# Mosaic-G5.net
KiCad netlist of a schematic drawn in Altium Designer
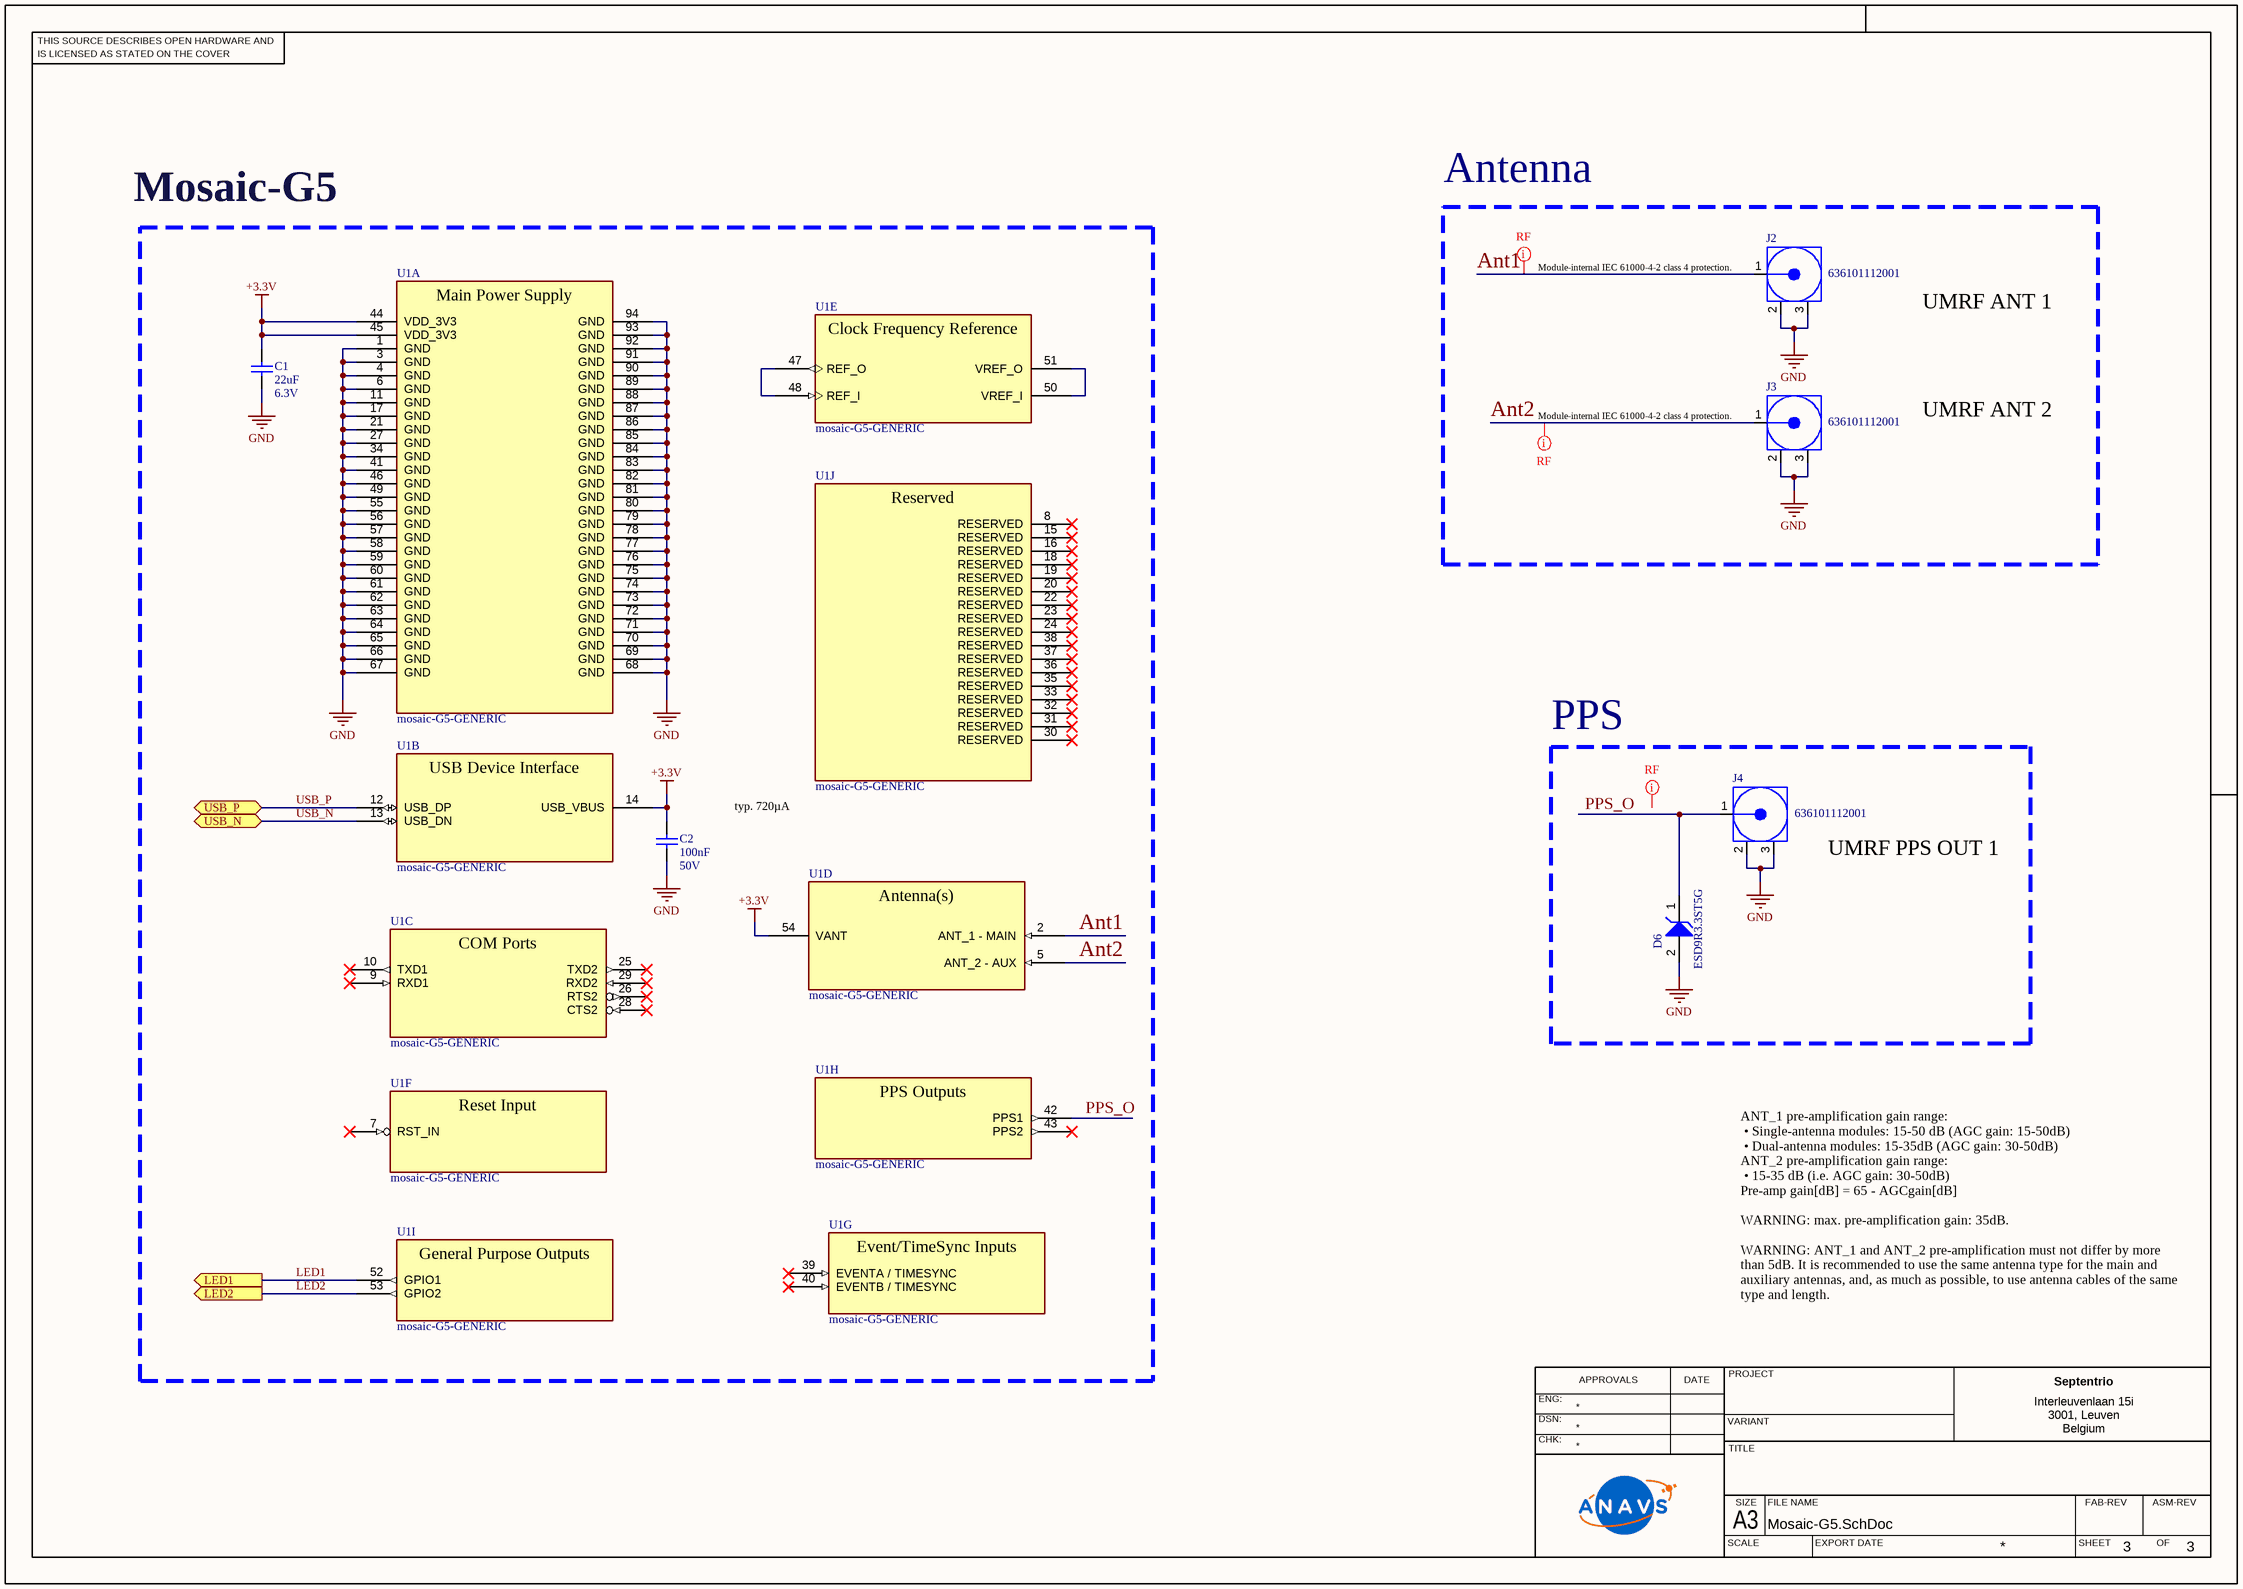
[diagram p0: Mosaic-G5.SchDoc]

(export (version "E")
  (design (tool "Eeschema 10.0.6"))
  (components
    (comp (ref "C1")
      (value "22uF")
      (footprint "CAPC1608X100X20ML10")
      (description "MLCC, 22 uF, 0603, 6.3 V, 20%, X5R")
      (fields
        (field (name "VOLTAGE") "6.3V")
        (field (name "TOLERANCE") "20%")
        (field (name "Comment") "C1608X5R0J226M080AC")
      )
      (libsource (lib "ANavS GmbH") (part "CAP"))
    )
    (comp (ref "C2")
      (value "GCM155R71H104KE02D")
      (footprint "CAP0402C")
      (description "MLCC, 100 nF, 0402, 50 V, 10%, X7R")
      (fields
        (field (name "CAPACITANCE") "100nF")
        (field (name "TOLERANCE") "10%")
        (field (name "VOLTAGE") "50V")
      )
      (libsource (lib "ANavS GmbH") (part "CAP"))
    )
    (comp (ref "D6")
      (value "ESD9R3.3ST5G")
      (footprint "ONSC-SOD-923-2-514AB-01_V")
      (description "ESD9R3.3S Series 4.8 V 0.5 pF Uni-Directional ESD Protection Diode - SOD-923")
      (libsource (lib "ANavS GmbH") (part "ONSC-K1A2-2_A"))
    )
    (comp (ref "J2")
      (value "636101112001")
      (footprint "63610111x001")
      (description "Rf Conn, Umrf, Jack, 50 Ohm, Pcb Rohs Compliant: Yes")
      (libsource (lib "ANavS GmbH") (part "Plug_2GND"))
    )
    (comp (ref "J3")
      (value "636101112001")
      (footprint "63610111x001")
      (description "Rf Conn, Umrf, Jack, 50 Ohm, Pcb Rohs Compliant: Yes")
      (libsource (lib "ANavS GmbH") (part "Plug_2GND"))
    )
    (comp (ref "J4")
      (value "636101112001")
      (footprint "63610111x001")
      (description "Rf Conn, Umrf, Jack, 50 Ohm, Pcb Rohs Compliant: Yes")
      (libsource (lib "ANavS GmbH") (part "Plug_2GND"))
    )
    (comp (ref "U1")
      (value "mosaic-G5-GENERIC")
      (footprint "mosaic-G5-GENERIC-Footprint")
      (description "mosaic-G5 GNSS Module - Low-power multi-band multi-constellation GNSS receiver.")
      (fields (field (name "MANUFACTURER") "septentrio"))
      (libsource (lib "ANavS GmbH") (part "mosaic-G5-Symbol"))
    )
  )
  (nets
    (net (code "1") (name "+3.3V") (class "Default")
      (node (ref "C1") (pin "2") (pinfunction "2_2") (pintype "passive"))
      (node (ref "C2") (pin "2") (pinfunction "2_2") (pintype "passive"))
      (node (ref "U1") (pin "14") (pinfunction "USB_VBUS_14") (pintype "power_in"))
      (node (ref "U1") (pin "44") (pinfunction "VDD_3V3_44") (pintype "power_in"))
      (node (ref "U1") (pin "45") (pinfunction "VDD_3V3_45") (pintype "power_in"))
      (node (ref "U1") (pin "54") (pinfunction "VANT_54") (pintype "power_in"))
    )
    (net (code "2") (name "/Ant1") (class "Default")
      (node (ref "J2") (pin "1") (pinfunction "Signal_1") (pintype "passive"))
      (node (ref "U1") (pin "2") (pinfunction "ANT_1_-_MAIN_2") (pintype "input"))
    )
    (net (code "3") (name "/Ant2") (class "Default")
      (node (ref "J3") (pin "1") (pinfunction "Signal_1") (pintype "passive"))
      (node (ref "U1") (pin "5") (pinfunction "ANT_2_-_AUX_5") (pintype "input"))
    )
    (net (code "4") (name "/LED1") (class "Default")
      (node (ref "U1") (pin "52") (pinfunction "GPIO1_52") (pintype "output"))
    )
    (net (code "5") (name "/LED2") (class "Default")
      (node (ref "U1") (pin "53") (pinfunction "GPIO2_53") (pintype "output"))
    )
    (net (code "6") (name "/PPS_O") (class "Default")
      (node (ref "D6") (pin "1") (pinfunction "K_1") (pintype "passive"))
      (node (ref "J4") (pin "1") (pinfunction "Signal_1") (pintype "passive"))
      (node (ref "U1") (pin "42") (pinfunction "PPS1_42") (pintype "output"))
    )
    (net (code "7") (name "/USB_N") (class "Default")
      (node (ref "U1") (pin "13") (pinfunction "USB_DN_13") (pintype "bidirectional"))
    )
    (net (code "8") (name "/USB_P") (class "Default")
      (node (ref "U1") (pin "12") (pinfunction "USB_DP_12") (pintype "bidirectional"))
    )
    (net (code "9") (name "GND") (class "Default")
      (node (ref "C1") (pin "1") (pinfunction "1_1") (pintype "passive"))
      (node (ref "C2") (pin "1") (pinfunction "1_1") (pintype "passive"))
      (node (ref "D6") (pin "2") (pinfunction "A_2") (pintype "passive"))
      (node (ref "J2") (pin "2") (pinfunction "GND_2") (pintype "passive"))
      (node (ref "J2") (pin "3") (pinfunction "GND_3") (pintype "passive"))
      (node (ref "J3") (pin "2") (pinfunction "GND_2") (pintype "passive"))
      (node (ref "J3") (pin "3") (pinfunction "GND_3") (pintype "passive"))
      (node (ref "J4") (pin "2") (pinfunction "GND_2") (pintype "passive"))
      (node (ref "J4") (pin "3") (pinfunction "GND_3") (pintype "passive"))
      (node (ref "U1") (pin "1") (pinfunction "GND_1") (pintype "power_in"))
      (node (ref "U1") (pin "11") (pinfunction "GND_11") (pintype "power_in"))
      (node (ref "U1") (pin "17") (pinfunction "GND_17") (pintype "power_in"))
      (node (ref "U1") (pin "21") (pinfunction "GND_21") (pintype "power_in"))
      (node (ref "U1") (pin "27") (pinfunction "GND_27") (pintype "power_in"))
      (node (ref "U1") (pin "3") (pinfunction "GND_3") (pintype "power_in"))
      (node (ref "U1") (pin "34") (pinfunction "GND_34") (pintype "power_in"))
      (node (ref "U1") (pin "4") (pinfunction "GND_4") (pintype "power_in"))
      (node (ref "U1") (pin "41") (pinfunction "GND_41") (pintype "power_in"))
      (node (ref "U1") (pin "46") (pinfunction "GND_46") (pintype "power_in"))
      (node (ref "U1") (pin "49") (pinfunction "GND_49") (pintype "power_in"))
      (node (ref "U1") (pin "55") (pinfunction "GND_55") (pintype "power_in"))
      (node (ref "U1") (pin "56") (pinfunction "GND_56") (pintype "power_in"))
      (node (ref "U1") (pin "57") (pinfunction "GND_57") (pintype "power_in"))
      (node (ref "U1") (pin "58") (pinfunction "GND_58") (pintype "power_in"))
      (node (ref "U1") (pin "59") (pinfunction "GND_59") (pintype "power_in"))
      (node (ref "U1") (pin "6") (pinfunction "GND_6") (pintype "power_in"))
      (node (ref "U1") (pin "60") (pinfunction "GND_60") (pintype "power_in"))
      (node (ref "U1") (pin "61") (pinfunction "GND_61") (pintype "power_in"))
      (node (ref "U1") (pin "62") (pinfunction "GND_62") (pintype "power_in"))
      (node (ref "U1") (pin "63") (pinfunction "GND_63") (pintype "power_in"))
      (node (ref "U1") (pin "64") (pinfunction "GND_64") (pintype "power_in"))
      (node (ref "U1") (pin "65") (pinfunction "GND_65") (pintype "power_in"))
      (node (ref "U1") (pin "66") (pinfunction "GND_66") (pintype "power_in"))
      (node (ref "U1") (pin "67") (pinfunction "GND_67") (pintype "power_in"))
      (node (ref "U1") (pin "68") (pinfunction "GND_68") (pintype "power_in"))
      (node (ref "U1") (pin "69") (pinfunction "GND_69") (pintype "power_in"))
      (node (ref "U1") (pin "70") (pinfunction "GND_70") (pintype "power_in"))
      (node (ref "U1") (pin "71") (pinfunction "GND_71") (pintype "power_in"))
      (node (ref "U1") (pin "72") (pinfunction "GND_72") (pintype "power_in"))
      (node (ref "U1") (pin "73") (pinfunction "GND_73") (pintype "power_in"))
      (node (ref "U1") (pin "74") (pinfunction "GND_74") (pintype "power_in"))
      (node (ref "U1") (pin "75") (pinfunction "GND_75") (pintype "power_in"))
      (node (ref "U1") (pin "76") (pinfunction "GND_76") (pintype "power_in"))
      (node (ref "U1") (pin "77") (pinfunction "GND_77") (pintype "power_in"))
      (node (ref "U1") (pin "78") (pinfunction "GND_78") (pintype "power_in"))
      (node (ref "U1") (pin "79") (pinfunction "GND_79") (pintype "power_in"))
      (node (ref "U1") (pin "80") (pinfunction "GND_80") (pintype "power_in"))
      (node (ref "U1") (pin "81") (pinfunction "GND_81") (pintype "power_in"))
      (node (ref "U1") (pin "82") (pinfunction "GND_82") (pintype "power_in"))
      (node (ref "U1") (pin "83") (pinfunction "GND_83") (pintype "power_in"))
      (node (ref "U1") (pin "84") (pinfunction "GND_84") (pintype "power_in"))
      (node (ref "U1") (pin "85") (pinfunction "GND_85") (pintype "power_in"))
      (node (ref "U1") (pin "86") (pinfunction "GND_86") (pintype "power_in"))
      (node (ref "U1") (pin "87") (pinfunction "GND_87") (pintype "power_in"))
      (node (ref "U1") (pin "88") (pinfunction "GND_88") (pintype "power_in"))
      (node (ref "U1") (pin "89") (pinfunction "GND_89") (pintype "power_in"))
      (node (ref "U1") (pin "90") (pinfunction "GND_90") (pintype "power_in"))
      (node (ref "U1") (pin "91") (pinfunction "GND_91") (pintype "power_in"))
      (node (ref "U1") (pin "92") (pinfunction "GND_92") (pintype "power_in"))
      (node (ref "U1") (pin "93") (pinfunction "GND_93") (pintype "power_in"))
      (node (ref "U1") (pin "94") (pinfunction "GND_94") (pintype "power_in"))
    )
    (net (code "10") (name "Net-(U1E-REF_I)") (class "Default")
      (node (ref "U1") (pin "47") (pinfunction "REF_O_47") (pintype "output"))
      (node (ref "U1") (pin "48") (pinfunction "REF_I_48") (pintype "input"))
    )
    (net (code "11") (name "Net-(U1E-VREF_I)") (class "Default")
      (node (ref "U1") (pin "50") (pinfunction "VREF_I_50") (pintype "power_in"))
      (node (ref "U1") (pin "51") (pinfunction "VREF_O_51") (pintype "power_in"))
    )
    (net (code "12") (name "unconnected-(U1C-CTS2-Pad28)") (class "Default")
      (node (ref "U1") (pin "28") (pinfunction "CTS2_28") (pintype "input+no_connect"))
    )
    (net (code "13") (name "unconnected-(U1C-RTS2-Pad26)") (class "Default")
      (node (ref "U1") (pin "26") (pinfunction "RTS2_26") (pintype "output+no_connect"))
    )
    (net (code "14") (name "unconnected-(U1C-RXD1-Pad9)") (class "Default")
      (node (ref "U1") (pin "9") (pinfunction "RXD1_9") (pintype "input+no_connect"))
    )
    (net (code "15") (name "unconnected-(U1C-RXD2-Pad29)") (class "Default")
      (node (ref "U1") (pin "29") (pinfunction "RXD2_29") (pintype "input+no_connect"))
    )
    (net (code "16") (name "unconnected-(U1C-TXD1-Pad10)") (class "Default")
      (node (ref "U1") (pin "10") (pinfunction "TXD1_10") (pintype "output+no_connect"))
    )
    (net (code "17") (name "unconnected-(U1C-TXD2-Pad25)") (class "Default")
      (node (ref "U1") (pin "25") (pinfunction "TXD2_25") (pintype "output+no_connect"))
    )
    (net (code "18") (name "unconnected-(U1F-RST_IN-Pad7)") (class "Default")
      (node (ref "U1") (pin "7") (pinfunction "RST_IN_7") (pintype "input+no_connect"))
    )
    (net (code "19") (name "unconnected-(U1G-EVENTA_{slash}_TIMESYNC-Pad39)") (class "Default")
      (node (ref "U1") (pin "39") (pinfunction "EVENTA_/_TIMESYNC_39") (pintype "input+no_connect"))
    )
    (net (code "20") (name "unconnected-(U1G-EVENTB_{slash}_TIMESYNC-Pad40)") (class "Default")
      (node (ref "U1") (pin "40") (pinfunction "EVENTB_/_TIMESYNC_40") (pintype "input+no_connect"))
    )
    (net (code "21") (name "unconnected-(U1H-PPS2-Pad43)") (class "Default")
      (node (ref "U1") (pin "43") (pinfunction "PPS2_43") (pintype "output+no_connect"))
    )
    (net (code "22") (name "unconnected-(U1J-RESERVED-Pad8)") (class "Default")
      (node (ref "U1") (pin "8") (pinfunction "RESERVED_8") (pintype "passive+no_connect"))
    )
    (net (code "23") (name "unconnected-(U1J-RESERVED-Pad15)") (class "Default")
      (node (ref "U1") (pin "15") (pinfunction "RESERVED_15") (pintype "passive+no_connect"))
    )
    (net (code "24") (name "unconnected-(U1J-RESERVED-Pad16)") (class "Default")
      (node (ref "U1") (pin "16") (pinfunction "RESERVED_16") (pintype "passive+no_connect"))
    )
    (net (code "25") (name "unconnected-(U1J-RESERVED-Pad18)") (class "Default")
      (node (ref "U1") (pin "18") (pinfunction "RESERVED_18") (pintype "passive+no_connect"))
    )
    (net (code "26") (name "unconnected-(U1J-RESERVED-Pad19)") (class "Default")
      (node (ref "U1") (pin "19") (pinfunction "RESERVED_19") (pintype "passive+no_connect"))
    )
    (net (code "27") (name "unconnected-(U1J-RESERVED-Pad20)") (class "Default")
      (node (ref "U1") (pin "20") (pinfunction "RESERVED_20") (pintype "passive+no_connect"))
    )
    (net (code "28") (name "unconnected-(U1J-RESERVED-Pad22)") (class "Default")
      (node (ref "U1") (pin "22") (pinfunction "RESERVED_22") (pintype "passive+no_connect"))
    )
    (net (code "29") (name "unconnected-(U1J-RESERVED-Pad23)") (class "Default")
      (node (ref "U1") (pin "23") (pinfunction "RESERVED_23") (pintype "passive+no_connect"))
    )
    (net (code "30") (name "unconnected-(U1J-RESERVED-Pad24)") (class "Default")
      (node (ref "U1") (pin "24") (pinfunction "RESERVED_24") (pintype "passive+no_connect"))
    )
    (net (code "31") (name "unconnected-(U1J-RESERVED-Pad30)") (class "Default")
      (node (ref "U1") (pin "30") (pinfunction "RESERVED_30") (pintype "passive+no_connect"))
    )
    (net (code "32") (name "unconnected-(U1J-RESERVED-Pad31)") (class "Default")
      (node (ref "U1") (pin "31") (pinfunction "RESERVED_31") (pintype "passive+no_connect"))
    )
    (net (code "33") (name "unconnected-(U1J-RESERVED-Pad32)") (class "Default")
      (node (ref "U1") (pin "32") (pinfunction "RESERVED_32") (pintype "passive+no_connect"))
    )
    (net (code "34") (name "unconnected-(U1J-RESERVED-Pad33)") (class "Default")
      (node (ref "U1") (pin "33") (pinfunction "RESERVED_33") (pintype "passive+no_connect"))
    )
    (net (code "35") (name "unconnected-(U1J-RESERVED-Pad35)") (class "Default")
      (node (ref "U1") (pin "35") (pinfunction "RESERVED_35") (pintype "passive+no_connect"))
    )
    (net (code "36") (name "unconnected-(U1J-RESERVED-Pad36)") (class "Default")
      (node (ref "U1") (pin "36") (pinfunction "RESERVED_36") (pintype "passive+no_connect"))
    )
    (net (code "37") (name "unconnected-(U1J-RESERVED-Pad37)") (class "Default")
      (node (ref "U1") (pin "37") (pinfunction "RESERVED_37") (pintype "passive+no_connect"))
    )
    (net (code "38") (name "unconnected-(U1J-RESERVED-Pad38)") (class "Default")
      (node (ref "U1") (pin "38") (pinfunction "RESERVED_38") (pintype "passive+no_connect"))
    )
  )
)
